# 4_EVB-A32S1-M_Sensing.net
KiCad netlist of a schematic drawn in Altium Designer
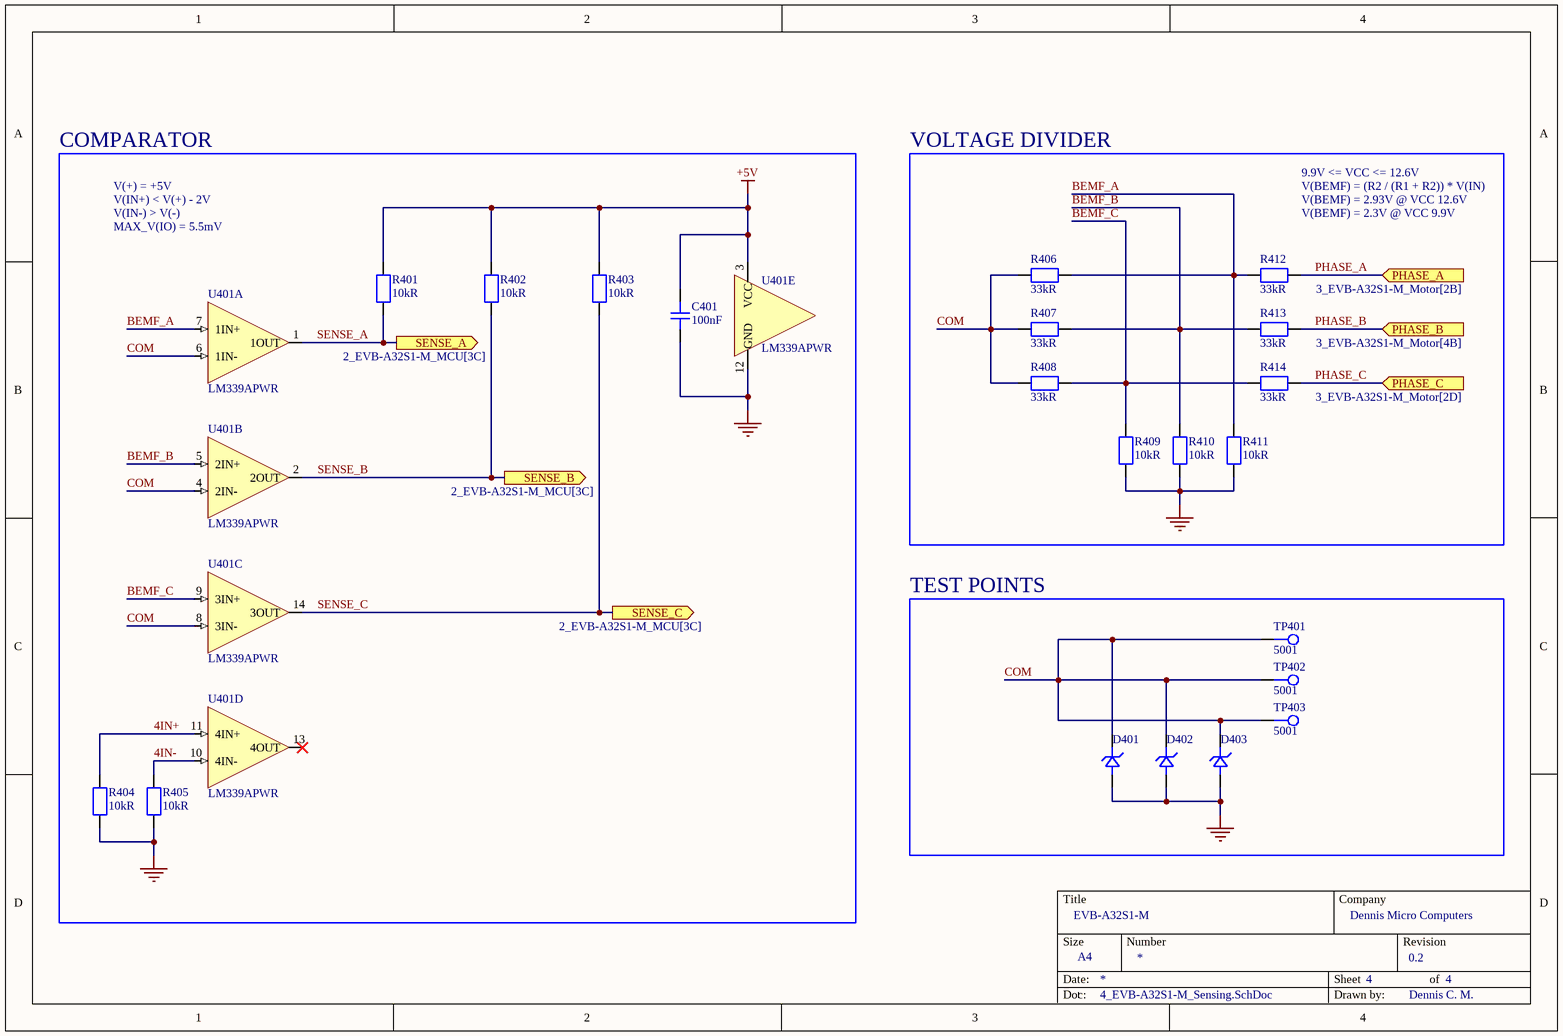
[diagram p0: 4_EVB-A32S1-M_Sensing.SchDoc]

(export (version "E")
  (design (tool "Eeschema 10.0.6"))
  (components
    (comp (ref "C401")
      (value "100nF")
      (footprint "C_Samsung_CL_0402_A")
      (description "Multilayer Ceramic Capacitor, 0.1 uF, 10 V, ± 10%, X7R, 0402 [1005 Metric]")
      (fields (field (name "TOLERANCE") "10%") (field (name "Comment") "CL05B104KP5NNNC"))
      (libsource (lib "Dennis Micro Computers") (part "C"))
    )
    (comp (ref "D401")
      (value "SMBJ15A-13-F")
      (footprint "D_TVS_Uni_Diodes_DO-214AA_B")
      (description "TVS Diode Single Uni-Dir 15V 600W 2-Pin SMB T/R / TVS DIODE 15VWM 24.4VC SMB")
      (libsource (lib "Dennis Micro Computers") (part "D_TVS_Uni"))
    )
    (comp (ref "D402")
      (value "SMBJ15A-13-F")
      (footprint "D_TVS_Uni_Diodes_DO-214AA_B")
      (description "TVS Diode Single Uni-Dir 15V 600W 2-Pin SMB T/R / TVS DIODE 15VWM 24.4VC SMB")
      (libsource (lib "Dennis Micro Computers") (part "D_TVS_Uni"))
    )
    (comp (ref "D403")
      (value "SMBJ15A-13-F")
      (footprint "D_TVS_Uni_Diodes_DO-214AA_B")
      (description "TVS Diode Single Uni-Dir 15V 600W 2-Pin SMB T/R / TVS DIODE 15VWM 24.4VC SMB")
      (libsource (lib "Dennis Micro Computers") (part "D_TVS_Uni"))
    )
    (comp (ref "R401")
      (value "10kR")
      (footprint "R_Yageo_RCL_0402_A")
      (description "SMD Chip Resistor, 10 kOhm, ± 1%, 62.5 mW, 0402 [1005 Metric], Thick Film, General Purpose")
      (fields (field (name "TOLERANCE") "1%") (field (name "Comment") "RC0402FR-0710KL"))
      (libsource (lib "Dennis Micro Computers") (part "R"))
    )
    (comp (ref "R402")
      (value "10kR")
      (footprint "R_Yageo_RCL_0402_A")
      (description "SMD Chip Resistor, 10 kOhm, ± 1%, 62.5 mW, 0402 [1005 Metric], Thick Film, General Purpose")
      (fields (field (name "TOLERANCE") "1%") (field (name "Comment") "RC0402FR-0710KL"))
      (libsource (lib "Dennis Micro Computers") (part "R"))
    )
    (comp (ref "R403")
      (value "10kR")
      (footprint "R_Yageo_RCL_0402_A")
      (description "SMD Chip Resistor, 10 kOhm, ± 1%, 62.5 mW, 0402 [1005 Metric], Thick Film, General Purpose")
      (fields (field (name "TOLERANCE") "1%") (field (name "Comment") "RC0402FR-0710KL"))
      (libsource (lib "Dennis Micro Computers") (part "R"))
    )
    (comp (ref "R404")
      (value "10kR")
      (footprint "R_Yageo_RCL_0402_A")
      (description "SMD Chip Resistor, 10 kOhm, ± 1%, 62.5 mW, 0402 [1005 Metric], Thick Film, General Purpose")
      (fields (field (name "TOLERANCE") "1%") (field (name "Comment") "RC0402FR-0710KL"))
      (libsource (lib "Dennis Micro Computers") (part "R"))
    )
    (comp (ref "R405")
      (value "10kR")
      (footprint "R_Yageo_RCL_0402_A")
      (description "SMD Chip Resistor, 10 kOhm, ± 1%, 62.5 mW, 0402 [1005 Metric], Thick Film, General Purpose")
      (fields (field (name "TOLERANCE") "1%") (field (name "Comment") "RC0402FR-0710KL"))
      (libsource (lib "Dennis Micro Computers") (part "R"))
    )
    (comp (ref "R406")
      (value "33kR")
      (footprint "R_Yageo_RCL_0402_A")
      (description "SMD Chip Resistor, 33 kOhm, ± 1%, 63 mW, 0402 [1005 Metric], Thick Film, General Purpose")
      (fields (field (name "TOLERANCE") "1%") (field (name "Comment") "RC0402FR-0733KL"))
      (libsource (lib "Dennis Micro Computers") (part "R"))
    )
    (comp (ref "R407")
      (value "33kR")
      (footprint "R_Yageo_RCL_0402_A")
      (description "SMD Chip Resistor, 33 kOhm, ± 1%, 63 mW, 0402 [1005 Metric], Thick Film, General Purpose")
      (fields (field (name "TOLERANCE") "1%") (field (name "Comment") "RC0402FR-0733KL"))
      (libsource (lib "Dennis Micro Computers") (part "R"))
    )
    (comp (ref "R408")
      (value "33kR")
      (footprint "R_Yageo_RCL_0402_A")
      (description "SMD Chip Resistor, 33 kOhm, ± 1%, 63 mW, 0402 [1005 Metric], Thick Film, General Purpose")
      (fields (field (name "TOLERANCE") "1%") (field (name "Comment") "RC0402FR-0733KL"))
      (libsource (lib "Dennis Micro Computers") (part "R"))
    )
    (comp (ref "R409")
      (value "10kR")
      (footprint "R_Yageo_RCL_0402_A")
      (description "SMD Chip Resistor, 10 kOhm, ± 1%, 62.5 mW, 0402 [1005 Metric], Thick Film, General Purpose")
      (fields (field (name "TOLERANCE") "1%") (field (name "Comment") "RC0402FR-0710KL"))
      (libsource (lib "Dennis Micro Computers") (part "R"))
    )
    (comp (ref "R410")
      (value "10kR")
      (footprint "R_Yageo_RCL_0402_A")
      (description "SMD Chip Resistor, 10 kOhm, ± 1%, 62.5 mW, 0402 [1005 Metric], Thick Film, General Purpose")
      (fields (field (name "TOLERANCE") "1%") (field (name "Comment") "RC0402FR-0710KL"))
      (libsource (lib "Dennis Micro Computers") (part "R"))
    )
    (comp (ref "R411")
      (value "10kR")
      (footprint "R_Yageo_RCL_0402_A")
      (description "SMD Chip Resistor, 10 kOhm, ± 1%, 62.5 mW, 0402 [1005 Metric], Thick Film, General Purpose")
      (fields (field (name "TOLERANCE") "1%") (field (name "Comment") "RC0402FR-0710KL"))
      (libsource (lib "Dennis Micro Computers") (part "R"))
    )
    (comp (ref "R412")
      (value "33kR")
      (footprint "R_Yageo_RCL_0402_A")
      (description "SMD Chip Resistor, 33 kOhm, ± 1%, 63 mW, 0402 [1005 Metric], Thick Film, General Purpose")
      (fields (field (name "TOLERANCE") "1%") (field (name "Comment") "RC0402FR-0733KL"))
      (libsource (lib "Dennis Micro Computers") (part "R"))
    )
    (comp (ref "R413")
      (value "33kR")
      (footprint "R_Yageo_RCL_0402_A")
      (description "SMD Chip Resistor, 33 kOhm, ± 1%, 63 mW, 0402 [1005 Metric], Thick Film, General Purpose")
      (fields (field (name "TOLERANCE") "1%") (field (name "Comment") "RC0402FR-0733KL"))
      (libsource (lib "Dennis Micro Computers") (part "R"))
    )
    (comp (ref "R414")
      (value "33kR")
      (footprint "R_Yageo_RCL_0402_A")
      (description "SMD Chip Resistor, 33 kOhm, ± 1%, 63 mW, 0402 [1005 Metric], Thick Film, General Purpose")
      (fields (field (name "TOLERANCE") "1%") (field (name "Comment") "RC0402FR-0733KL"))
      (libsource (lib "Dennis Micro Computers") (part "R"))
    )
    (comp (ref "TP401")
      (value "5001")
      (footprint "TP_Keystone_TH")
      (libsource (lib "Dennis Micro Computers") (part "TP"))
    )
    (comp (ref "TP402")
      (value "5001")
      (footprint "TP_Keystone_TH")
      (libsource (lib "Dennis Micro Computers") (part "TP"))
    )
    (comp (ref "TP403")
      (value "5001")
      (footprint "TP_Keystone_TH")
      (libsource (lib "Dennis Micro Computers") (part "TP"))
    )
    (comp (ref "U401")
      (value "LM339APWR")
      (footprint "U_TI_14-TSSOP-5.00x4.40mm_0.62mm_B")
      (description "Precision quad differential comparator, commercial grade 14-TSSOP 0 to 70")
      (libsource (lib "Dennis Micro Computers") (part "U_LM339APWR"))
    )
  )
  (nets
    (net (code "1") (name "+5V") (class "Default")
      (node (ref "C401") (pin "2") (pinfunction "2_2") (pintype "passive"))
      (node (ref "R401") (pin "2") (pinfunction "2_2") (pintype "passive"))
      (node (ref "R402") (pin "2") (pinfunction "2_2") (pintype "passive"))
      (node (ref "R403") (pin "2") (pinfunction "2_2") (pintype "passive"))
      (node (ref "U401") (pin "3") (pinfunction "VCC_3") (pintype "power_in"))
    )
    (net (code "2") (name "/4IN+") (class "Default")
      (node (ref "R404") (pin "2") (pinfunction "2_2") (pintype "passive"))
      (node (ref "U401") (pin "11") (pinfunction "4IN+_11") (pintype "input"))
    )
    (net (code "3") (name "/4IN-") (class "Default")
      (node (ref "R405") (pin "2") (pinfunction "2_2") (pintype "passive"))
      (node (ref "U401") (pin "10") (pinfunction "4IN-_10") (pintype "input"))
    )
    (net (code "4") (name "/BEMF_A") (class "Default")
      (node (ref "R406") (pin "2") (pinfunction "2_2") (pintype "passive"))
      (node (ref "R411") (pin "2") (pinfunction "2_2") (pintype "passive"))
      (node (ref "R412") (pin "1") (pinfunction "1_1") (pintype "passive"))
      (node (ref "U401") (pin "7") (pinfunction "1IN+_7") (pintype "input"))
    )
    (net (code "5") (name "/BEMF_B") (class "Default")
      (node (ref "R407") (pin "2") (pinfunction "2_2") (pintype "passive"))
      (node (ref "R410") (pin "2") (pinfunction "2_2") (pintype "passive"))
      (node (ref "R413") (pin "1") (pinfunction "1_1") (pintype "passive"))
      (node (ref "U401") (pin "5") (pinfunction "2IN+_5") (pintype "input"))
    )
    (net (code "6") (name "/BEMF_C") (class "Default")
      (node (ref "R408") (pin "2") (pinfunction "2_2") (pintype "passive"))
      (node (ref "R409") (pin "2") (pinfunction "2_2") (pintype "passive"))
      (node (ref "R414") (pin "1") (pinfunction "1_1") (pintype "passive"))
      (node (ref "U401") (pin "9") (pinfunction "3IN+_9") (pintype "input"))
    )
    (net (code "7") (name "/COM") (class "Default")
      (node (ref "D401") (pin "1") (pinfunction "1_1") (pintype "passive"))
      (node (ref "D402") (pin "1") (pinfunction "1_1") (pintype "passive"))
      (node (ref "D403") (pin "1") (pinfunction "1_1") (pintype "passive"))
      (node (ref "R406") (pin "1") (pinfunction "1_1") (pintype "passive"))
      (node (ref "R407") (pin "1") (pinfunction "1_1") (pintype "passive"))
      (node (ref "R408") (pin "1") (pinfunction "1_1") (pintype "passive"))
      (node (ref "TP401") (pin "1") (pinfunction "1_1") (pintype "passive"))
      (node (ref "TP402") (pin "1") (pinfunction "1_1") (pintype "passive"))
      (node (ref "TP403") (pin "1") (pinfunction "1_1") (pintype "passive"))
      (node (ref "U401") (pin "4") (pinfunction "2IN-_4") (pintype "input"))
      (node (ref "U401") (pin "6") (pinfunction "1IN-_6") (pintype "input"))
      (node (ref "U401") (pin "8") (pinfunction "3IN-_8") (pintype "input"))
    )
    (net (code "8") (name "/PHASE_A") (class "Default")
      (node (ref "R412") (pin "2") (pinfunction "2_2") (pintype "passive"))
    )
    (net (code "9") (name "/PHASE_B") (class "Default")
      (node (ref "R413") (pin "2") (pinfunction "2_2") (pintype "passive"))
    )
    (net (code "10") (name "/PHASE_C") (class "Default")
      (node (ref "R414") (pin "2") (pinfunction "2_2") (pintype "passive"))
    )
    (net (code "11") (name "/SENSE_A") (class "Default")
      (node (ref "R401") (pin "1") (pinfunction "1_1") (pintype "passive"))
      (node (ref "U401") (pin "1") (pinfunction "1OUT_1") (pintype "open_collector"))
    )
    (net (code "12") (name "/SENSE_B") (class "Default")
      (node (ref "R402") (pin "1") (pinfunction "1_1") (pintype "passive"))
      (node (ref "U401") (pin "2") (pinfunction "2OUT_2") (pintype "open_collector"))
    )
    (net (code "13") (name "/SENSE_C") (class "Default")
      (node (ref "R403") (pin "1") (pinfunction "1_1") (pintype "passive"))
      (node (ref "U401") (pin "14") (pinfunction "3OUT_14") (pintype "open_collector"))
    )
    (net (code "14") (name "GND") (class "Default")
      (node (ref "C401") (pin "1") (pinfunction "1_1") (pintype "passive"))
      (node (ref "D401") (pin "2") (pinfunction "2_2") (pintype "passive"))
      (node (ref "D402") (pin "2") (pinfunction "2_2") (pintype "passive"))
      (node (ref "D403") (pin "2") (pinfunction "2_2") (pintype "passive"))
      (node (ref "R404") (pin "1") (pinfunction "1_1") (pintype "passive"))
      (node (ref "R405") (pin "1") (pinfunction "1_1") (pintype "passive"))
      (node (ref "R409") (pin "1") (pinfunction "1_1") (pintype "passive"))
      (node (ref "R410") (pin "1") (pinfunction "1_1") (pintype "passive"))
      (node (ref "R411") (pin "1") (pinfunction "1_1") (pintype "passive"))
      (node (ref "U401") (pin "12") (pinfunction "GND_12") (pintype "power_in"))
    )
    (net (code "15") (name "unconnected-(U401D-4OUT-Pad13)") (class "Default")
      (node (ref "U401") (pin "13") (pinfunction "4OUT_13") (pintype "open_collector+no_connect"))
    )
  )
)
